# power_switch_1.net
KiCad netlist of a schematic drawn in EAGLE
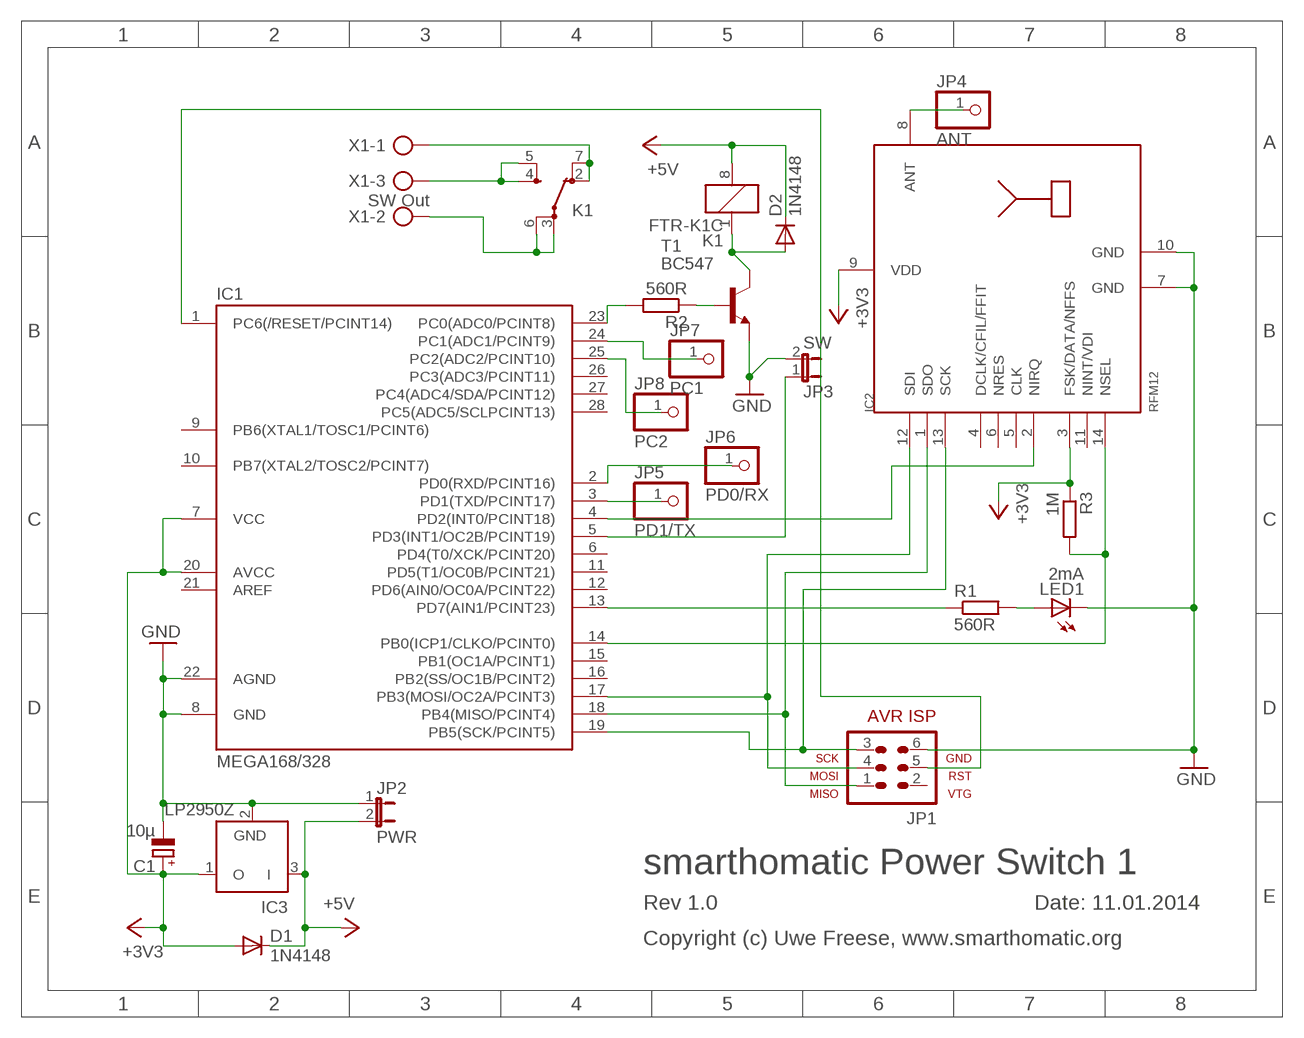
[diagram p0: schematic, sheet 1]

(export (version "E")
  (design (tool "Eeschema 10.0.6"))
  (components
    (comp (ref "C1")
      (value "10µ")
      (footprint "eagle-import:E1,8-4")
      (libsource (lib "eagle-import") (part "CPOL-EUE1.8-4"))
    )
    (comp (ref "D1")
      (value "1N4148")
      (footprint "eagle-import:DO35-7")
      (libsource (lib "eagle-import") (part "1N4148DO35-7"))
    )
    (comp (ref "D2")
      (value "1N4148")
      (footprint "eagle-import:DO35-7")
      (libsource (lib "eagle-import") (part "1N4148DO35-7"))
    )
    (comp (ref "IC1")
      (value "MEGA168/328")
      (footprint "eagle-import:DIL28-3")
      (libsource (lib "eagle-import") (part "MEGA48/88/168-PU"))
    )
    (comp (ref "IC2")
      (value "RFM12")
      (footprint "eagle-import:RFM")
      (libsource (lib "eagle-import") (part "RFM12"))
    )
    (comp (ref "IC3")
      (value "LP2950Z")
      (footprint "eagle-import:TO92")
      (libsource (lib "eagle-import") (part "LP2950Z"))
    )
    (comp (ref "JP1")
      (value "AVR-ISP-6")
      (footprint "eagle-import:AVR-ISP-6")
      (libsource (lib "eagle-import") (part "AVR-ISP-6"))
    )
    (comp (ref "JP2")
      (value "PWR")
      (footprint "eagle-import:JP1")
      (libsource (lib "eagle-import") (part "JP1E"))
    )
    (comp (ref "JP3")
      (value "SW")
      (footprint "eagle-import:JP1")
      (libsource (lib "eagle-import") (part "JP1E"))
    )
    (comp (ref "JP4")
      (value "ANT")
      (footprint "eagle-import:1X01")
      (libsource (lib "eagle-import") (part "PINHD-1X1"))
    )
    (comp (ref "JP5")
      (value "PD1/TX")
      (footprint "eagle-import:1X01")
      (libsource (lib "eagle-import") (part "PINHD-1X1"))
    )
    (comp (ref "JP6")
      (value "PD0/RX")
      (footprint "eagle-import:1X01")
      (libsource (lib "eagle-import") (part "PINHD-1X1"))
    )
    (comp (ref "JP7")
      (value "PC1")
      (footprint "eagle-import:1X01")
      (libsource (lib "eagle-import") (part "PINHD-1X1"))
    )
    (comp (ref "JP8")
      (value "PC2")
      (footprint "eagle-import:1X01")
      (libsource (lib "eagle-import") (part "PINHD-1X1"))
    )
    (comp (ref "K1")
      (value "FTR-K1C")
      (footprint "eagle-import:FTR-K1C")
      (libsource (lib "eagle-import") (part "FTR-K1C"))
    )
    (comp (ref "LED1")
      (value "2mA")
      (footprint "eagle-import:LED3MM")
      (libsource (lib "eagle-import") (part "LED3MM"))
    )
    (comp (ref "R1")
      (value "560R")
      (footprint "eagle-import:0207_7")
      (libsource (lib "eagle-import") (part "R-EU_0207/7"))
    )
    (comp (ref "R2")
      (value "560R")
      (footprint "eagle-import:0207_7")
      (libsource (lib "eagle-import") (part "R-EU_0207/7"))
    )
    (comp (ref "R3")
      (value "1M")
      (footprint "eagle-import:0207_7")
      (libsource (lib "eagle-import") (part "R-EU_0207/7"))
    )
    (comp (ref "T1")
      (value "BC547")
      (footprint "eagle-import:TO92")
      (libsource (lib "eagle-import") (part "BC547"))
    )
    (comp (ref "X1")
      (value "SW Out")
      (footprint "eagle-import:AK500_3")
      (libsource (lib "eagle-import") (part "AK500/3"))
    )
  )
  (nets
    (net (code "1") (name "+3V3") (class "Default")
      (node (ref "C1") (pin "+") (pinfunction "+_+") (pintype "passive"))
      (node (ref "D1") (pin "A") (pinfunction "A_A") (pintype "passive"))
      (node (ref "IC1") (pin "20") (pinfunction "AVCC_20") (pintype "passive"))
      (node (ref "IC1") (pin "7") (pinfunction "VCC_7") (pintype "power_in"))
      (node (ref "IC2") (pin "3") (pinfunction "FSK/DATA/NFFS_3") (pintype "bidirectional"))
      (node (ref "IC2") (pin "9") (pinfunction "VDD_9") (pintype "power_in"))
      (node (ref "IC3") (pin "1") (pinfunction "O_1") (pintype "input"))
      (node (ref "R3") (pin "1") (pinfunction "1_1") (pintype "passive"))
    )
    (net (code "2") (name "+5V") (class "Default")
      (node (ref "D1") (pin "C") (pinfunction "C_C") (pintype "passive"))
      (node (ref "D2") (pin "C") (pinfunction "C_C") (pintype "passive"))
      (node (ref "IC3") (pin "3") (pinfunction "I_3") (pintype "input"))
      (node (ref "JP2") (pin "2") (pinfunction "2_2") (pintype "passive"))
      (node (ref "K1") (pin "8") (pinfunction "2_8") (pintype "passive"))
    )
    (net (code "3") (name "GND") (class "Default")
      (node (ref "C1") (pin "-") (pinfunction "-_-") (pintype "passive"))
      (node (ref "IC1") (pin "22") (pinfunction "AGND_22") (pintype "power_in"))
      (node (ref "IC1") (pin "8") (pinfunction "GND_8") (pintype "power_in"))
      (node (ref "IC2") (pin "10") (pinfunction "GND_10") (pintype "power_in"))
      (node (ref "IC2") (pin "7") (pinfunction "GND_7") (pintype "power_in"))
      (node (ref "IC3") (pin "2") (pinfunction "GND_2") (pintype "power_in"))
      (node (ref "JP1") (pin "6") (pinfunction "6_6") (pintype "passive"))
      (node (ref "JP2") (pin "1") (pinfunction "1_1") (pintype "passive"))
      (node (ref "JP3") (pin "2") (pinfunction "2_2") (pintype "passive"))
      (node (ref "LED1") (pin "K") (pinfunction "C_K") (pintype "passive"))
      (node (ref "T1") (pin "1") (pinfunction "E_1") (pintype "passive"))
    )
    (net (code "4") (name "Net-(IC1-PB0(ICP1{slash}CLKO{slash}PCINT0))") (class "Default")
      (node (ref "IC1") (pin "14") (pinfunction "PB0(ICP1/CLKO/PCINT0)_14") (pintype "bidirectional"))
      (node (ref "IC2") (pin "14") (pinfunction "NSEL_14") (pintype "bidirectional"))
      (node (ref "R3") (pin "2") (pinfunction "2_2") (pintype "passive"))
    )
    (net (code "5") (name "Net-(IC1-PB3(MOSI{slash}OC2A{slash}PCINT3))") (class "Default")
      (node (ref "IC1") (pin "17") (pinfunction "PB3(MOSI/OC2A/PCINT3)_17") (pintype "bidirectional"))
      (node (ref "IC2") (pin "12") (pinfunction "SDI_12") (pintype "bidirectional"))
      (node (ref "JP1") (pin "4") (pinfunction "4_4") (pintype "passive"))
    )
    (net (code "6") (name "Net-(IC1-PB4(MISO{slash}PCINT4))") (class "Default")
      (node (ref "IC1") (pin "18") (pinfunction "PB4(MISO/PCINT4)_18") (pintype "bidirectional"))
      (node (ref "IC2") (pin "1") (pinfunction "SDO_1") (pintype "bidirectional"))
      (node (ref "JP1") (pin "1") (pinfunction "1_1") (pintype "passive"))
    )
    (net (code "7") (name "Net-(IC1-PB5(SCK{slash}PCINT5))") (class "Default")
      (node (ref "IC1") (pin "19") (pinfunction "PB5(SCK/PCINT5)_19") (pintype "bidirectional"))
      (node (ref "IC2") (pin "13") (pinfunction "SCK_13") (pintype "bidirectional"))
      (node (ref "JP1") (pin "3") (pinfunction "3_3") (pintype "passive"))
    )
    (net (code "8") (name "Net-(IC1-PC0(ADC0{slash}PCINT8))") (class "Default")
      (node (ref "IC1") (pin "23") (pinfunction "PC0(ADC0/PCINT8)_23") (pintype "bidirectional"))
      (node (ref "R2") (pin "2") (pinfunction "2_2") (pintype "passive"))
    )
    (net (code "9") (name "Net-(IC1-PC1(ADC1{slash}PCINT9))") (class "Default")
      (node (ref "IC1") (pin "24") (pinfunction "PC1(ADC1/PCINT9)_24") (pintype "bidirectional"))
      (node (ref "JP7") (pin "1") (pinfunction "1_1") (pintype "passive"))
    )
    (net (code "10") (name "Net-(IC1-PC2(ADC2{slash}PCINT10))") (class "Default")
      (node (ref "IC1") (pin "25") (pinfunction "PC2(ADC2/PCINT10)_25") (pintype "bidirectional"))
      (node (ref "JP8") (pin "1") (pinfunction "1_1") (pintype "passive"))
    )
    (net (code "11") (name "Net-(IC1-PC6({slash}RESET{slash}PCINT14))") (class "Default")
      (node (ref "IC1") (pin "1") (pinfunction "PC6(/RESET/PCINT14)_1") (pintype "bidirectional"))
      (node (ref "JP1") (pin "5") (pinfunction "5_5") (pintype "passive"))
    )
    (net (code "12") (name "Net-(IC1-PD0(RXD{slash}PCINT16))") (class "Default")
      (node (ref "IC1") (pin "2") (pinfunction "PD0(RXD/PCINT16)_2") (pintype "bidirectional"))
      (node (ref "JP6") (pin "1") (pinfunction "1_1") (pintype "passive"))
    )
    (net (code "13") (name "Net-(IC1-PD1(TXD{slash}PCINT17))") (class "Default")
      (node (ref "IC1") (pin "3") (pinfunction "PD1(TXD/PCINT17)_3") (pintype "bidirectional"))
      (node (ref "JP5") (pin "1") (pinfunction "1_1") (pintype "passive"))
    )
    (net (code "14") (name "Net-(IC1-PD2(INT0{slash}PCINT18))") (class "Default")
      (node (ref "IC1") (pin "4") (pinfunction "PD2(INT0/PCINT18)_4") (pintype "bidirectional"))
      (node (ref "IC2") (pin "2") (pinfunction "NIRQ_2") (pintype "bidirectional"))
    )
    (net (code "15") (name "Net-(IC1-PD3(INT1{slash}OC2B{slash}PCINT19))") (class "Default")
      (node (ref "IC1") (pin "5") (pinfunction "PD3(INT1/OC2B/PCINT19)_5") (pintype "bidirectional"))
      (node (ref "JP3") (pin "1") (pinfunction "1_1") (pintype "passive"))
    )
    (net (code "16") (name "Net-(IC1-PD7(AIN1{slash}PCINT23))") (class "Default")
      (node (ref "IC1") (pin "13") (pinfunction "PD7(AIN1/PCINT23)_13") (pintype "bidirectional"))
      (node (ref "R1") (pin "1") (pinfunction "1_1") (pintype "passive"))
    )
    (net (code "17") (name "Net-(IC2-ANT)") (class "Default")
      (node (ref "IC2") (pin "8") (pinfunction "ANT_8") (pintype "output"))
      (node (ref "JP4") (pin "1") (pinfunction "1_1") (pintype "passive"))
    )
    (net (code "18") (name "Net-(K1A-OA)") (class "Default")
      (node (ref "K1") (pin "2") (pinfunction "OA_2") (pintype "passive"))
      (node (ref "K1") (pin "7") (pinfunction "OB_7") (pintype "passive"))
      (node (ref "X1") (pin "1") (pinfunction "KL_1") (pintype "passive"))
    )
    (net (code "19") (name "Net-(K1A-PA)") (class "Default")
      (node (ref "K1") (pin "3") (pinfunction "PA_3") (pintype "passive"))
      (node (ref "K1") (pin "6") (pinfunction "PB_6") (pintype "passive"))
      (node (ref "X1") (pin "2") (pinfunction "KL_2") (pintype "passive"))
    )
    (net (code "20") (name "Net-(K1A-SA)") (class "Default")
      (node (ref "K1") (pin "4") (pinfunction "SA_4") (pintype "passive"))
      (node (ref "K1") (pin "5") (pinfunction "SB_5") (pintype "passive"))
      (node (ref "X1") (pin "3") (pinfunction "KL_3") (pintype "passive"))
    )
    (net (code "21") (name "Net-(LED1-PadA)") (class "Default")
      (node (ref "LED1") (pin "A") (pinfunction "A_A") (pintype "passive"))
      (node (ref "R1") (pin "2") (pinfunction "2_2") (pintype "passive"))
    )
    (net (code "22") (name "Net-(T1-B)") (class "Default")
      (node (ref "R2") (pin "1") (pinfunction "1_1") (pintype "passive"))
      (node (ref "T1") (pin "2") (pinfunction "B_2") (pintype "passive"))
    )
    (net (code "23") (name "Net-(T1-C)") (class "Default")
      (node (ref "D2") (pin "A") (pinfunction "A_A") (pintype "passive"))
      (node (ref "K1") (pin "1") (pinfunction "1_1") (pintype "passive"))
      (node (ref "T1") (pin "3") (pinfunction "C_3") (pintype "passive"))
    )
    (net (code "24") (name "unconnected-(IC1-AREF-Pad21)") (class "Default")
      (node (ref "IC1") (pin "21") (pinfunction "AREF_21") (pintype "passive"))
    )
    (net (code "25") (name "unconnected-(IC1-PB1(OC1A{slash}PCINT1)-Pad15)") (class "Default")
      (node (ref "IC1") (pin "15") (pinfunction "PB1(OC1A/PCINT1)_15") (pintype "bidirectional"))
    )
    (net (code "26") (name "unconnected-(IC1-PB2(SS{slash}OC1B{slash}PCINT2)-Pad16)") (class "Default")
      (node (ref "IC1") (pin "16") (pinfunction "PB2(SS/OC1B/PCINT2)_16") (pintype "bidirectional"))
    )
    (net (code "27") (name "unconnected-(IC1-PB6(XTAL1{slash}TOSC1{slash}PCINT6)-Pad9)") (class "Default")
      (node (ref "IC1") (pin "9") (pinfunction "PB6(XTAL1/TOSC1/PCINT6)_9") (pintype "bidirectional"))
    )
    (net (code "28") (name "unconnected-(IC1-PB7(XTAL2{slash}TOSC2{slash}PCINT7)-Pad10)") (class "Default")
      (node (ref "IC1") (pin "10") (pinfunction "PB7(XTAL2/TOSC2/PCINT7)_10") (pintype "bidirectional"))
    )
    (net (code "29") (name "unconnected-(IC1-PC3(ADC3{slash}PCINT11)-Pad26)") (class "Default")
      (node (ref "IC1") (pin "26") (pinfunction "PC3(ADC3/PCINT11)_26") (pintype "bidirectional"))
    )
    (net (code "30") (name "unconnected-(IC1-PC4(ADC4{slash}SDA{slash}PCINT12)-Pad27)") (class "Default")
      (node (ref "IC1") (pin "27") (pinfunction "PC4(ADC4/SDA/PCINT12)_27") (pintype "bidirectional"))
    )
    (net (code "31") (name "unconnected-(IC1-PC5(ADC5{slash}SCLPCINT13)-Pad28)") (class "Default")
      (node (ref "IC1") (pin "28") (pinfunction "PC5(ADC5/SCLPCINT13)_28") (pintype "bidirectional"))
    )
    (net (code "32") (name "unconnected-(IC1-PD4(T0{slash}XCK{slash}PCINT20)-Pad6)") (class "Default")
      (node (ref "IC1") (pin "6") (pinfunction "PD4(T0/XCK/PCINT20)_6") (pintype "bidirectional"))
    )
    (net (code "33") (name "unconnected-(IC1-PD5(T1{slash}OC0B{slash}PCINT21)-Pad11)") (class "Default")
      (node (ref "IC1") (pin "11") (pinfunction "PD5(T1/OC0B/PCINT21)_11") (pintype "bidirectional"))
    )
    (net (code "34") (name "unconnected-(IC1-PD6(AIN0{slash}OC0A{slash}PCINT22)-Pad12)") (class "Default")
      (node (ref "IC1") (pin "12") (pinfunction "PD6(AIN0/OC0A/PCINT22)_12") (pintype "bidirectional"))
    )
    (net (code "35") (name "unconnected-(IC2-CLK-Pad5)") (class "Default")
      (node (ref "IC2") (pin "5") (pinfunction "CLK_5") (pintype "bidirectional"))
    )
    (net (code "36") (name "unconnected-(IC2-DCLK{slash}CFIL{slash}FFIT-Pad4)") (class "Default")
      (node (ref "IC2") (pin "4") (pinfunction "DCLK/CFIL/FFIT_4") (pintype "bidirectional"))
    )
    (net (code "37") (name "unconnected-(IC2-NINT{slash}VDI-Pad11)") (class "Default")
      (node (ref "IC2") (pin "11") (pinfunction "NINT/VDI_11") (pintype "bidirectional"))
    )
    (net (code "38") (name "unconnected-(IC2-NRES-Pad6)") (class "Default")
      (node (ref "IC2") (pin "6") (pinfunction "NRES_6") (pintype "bidirectional"))
    )
    (net (code "39") (name "unconnected-(JP1-Pad2)") (class "Default")
      (node (ref "JP1") (pin "2") (pinfunction "2_2") (pintype "passive"))
    )
  )
)
